# LMR514205V.net
KiCad netlist of a schematic drawn in Altium Designer
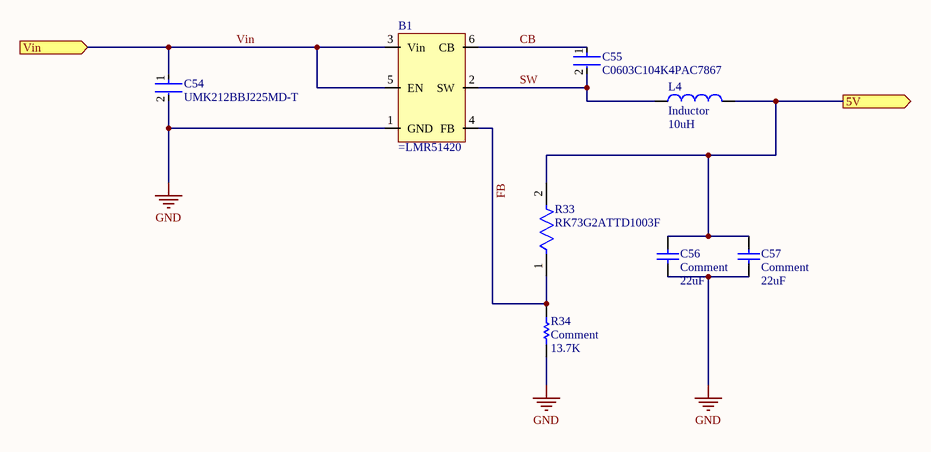
[diagram p0: LMR514205V.SchDoc]

(export (version "E")
  (design (tool "Eeschema 10.0.6"))
  (components
    (comp (ref "B1")
      (value "~")
      (footprint "LMR51420:PCBComponent_1")
      (libsource (lib "LMR51420") (part "Component_1"))
    )
    (comp (ref "C54")
      (value "UMK212BBJ225MD-T")
      (footprint "FP-0805-L_2_0_0_2-W_1_25-IPC_A")
      (description "Multilayer Ceramic Capacitor 2.2uF 50V X5R 20% SMD 0803 T/R")
      (fields (field (name "TOLERANCE") "20%"))
      (libsource (lib "Altium Content Vault") (part "02cd4be3c70576c341d710602a673aa"))
    )
    (comp (ref "C55")
      (value "C0603C104K4PAC7867")
      (footprint "FP-C0603C-CF-MFG")
      (description "CAP CER 0.1UF 16V X5R 0603")
      (fields
        (field (name "OCTOPART") "https://octopart.com/c0603c104k4pactu-kemet-12592163")
        (field (name "MANUFACTURER") "KEMET")
      )
      (libsource (lib "Altium Content Vault") (part "b4654b650e69147ec39a6b967a45e02"))
    )
    (comp (ref "C56")
      (value "Comment")
      (footprint "Cap22uF_C1206C226M4PAC7800")
      (description "Capacitor")
      (fields (field (name "ALTIUM_VALUE") "22uF") (field (name "PUBLISHER") "Altium Limited"))
      (libsource (lib "Miscellaneous Devices") (part "Cap"))
    )
    (comp (ref "C57")
      (value "Comment")
      (footprint "Cap22uF_C1206C226M4PAC7800")
      (description "Capacitor")
      (fields (field (name "ALTIUM_VALUE") "22uF") (field (name "PUBLISHER") "Altium Limited"))
      (libsource (lib "Miscellaneous Devices") (part "Cap"))
    )
    (comp (ref "L4")
      (value "Inductor")
      (footprint "0402-A")
      (fields (field (name "ALTIUM_VALUE") "10uH") (field (name "PUBLISHER") "Altium Limited"))
      (libsource (lib "Miscellaneous Devices") (part "Inductor"))
    )
    (comp (ref "R33")
      (value "RK73G2ATTD1003F")
      (footprint "FP-RK73G2A-IPC_A")
      (description "100kΩ ±1% 0.125W Chip Resistor 0805 Thick Film AEC-Q200 Qualified")
      (fields (field (name "TOLERANCE") "1%"))
      (libsource (lib "Altium Content Vault") (part "1029c3af85768c4190bb7ad29bc67b5"))
    )
    (comp (ref "R34")
      (value "Comment")
      (footprint "RMCF0805FT13K7_13.7k")
      (description "Resistor")
      (fields (field (name "ALTIUM_VALUE") "13.7K") (field (name "PUBLISHER") "Altium Limited"))
      (libsource (lib "Miscellaneous Devices") (part "Res1"))
    )
  )
  (nets
    (net (code "1") (name "/5V") (class "Default")
      (node (ref "C56") (pin "2") (pinfunction "2_2") (pintype "passive"))
      (node (ref "C57") (pin "2") (pinfunction "2_2") (pintype "passive"))
      (node (ref "L4") (pin "2") (pinfunction "2_2") (pintype "passive"))
      (node (ref "R33") (pin "2") (pinfunction "2_2") (pintype "passive"))
    )
    (net (code "2") (name "/CB") (class "Default")
      (node (ref "B1") (pin "6") (pinfunction "CB_6") (pintype "passive"))
      (node (ref "C55") (pin "1") (pinfunction "1_1") (pintype "passive"))
    )
    (net (code "3") (name "/FB") (class "Default")
      (node (ref "B1") (pin "4") (pinfunction "FB_4") (pintype "passive"))
      (node (ref "R33") (pin "1") (pinfunction "1_1") (pintype "passive"))
      (node (ref "R34") (pin "2") (pinfunction "2_2") (pintype "passive"))
    )
    (net (code "4") (name "/SW") (class "Default")
      (node (ref "B1") (pin "2") (pinfunction "SW_2") (pintype "passive"))
      (node (ref "C55") (pin "2") (pinfunction "2_2") (pintype "passive"))
      (node (ref "L4") (pin "1") (pinfunction "1_1") (pintype "passive"))
    )
    (net (code "5") (name "/Vin") (class "Default")
      (node (ref "B1") (pin "3") (pinfunction "Vin_3") (pintype "passive"))
      (node (ref "B1") (pin "5") (pinfunction "EN_5") (pintype "passive"))
      (node (ref "C54") (pin "1") (pinfunction "1_1") (pintype "passive"))
    )
    (net (code "6") (name "GND") (class "Default")
      (node (ref "B1") (pin "1") (pinfunction "GND_1") (pintype "passive"))
      (node (ref "C54") (pin "2") (pinfunction "2_2") (pintype "passive"))
      (node (ref "C56") (pin "1") (pinfunction "1_1") (pintype "passive"))
      (node (ref "C57") (pin "1") (pinfunction "1_1") (pintype "passive"))
      (node (ref "R34") (pin "1") (pinfunction "1_1") (pintype "passive"))
    )
  )
)
